# module_board.net
KiCad netlist of a schematic drawn in Altium Designer
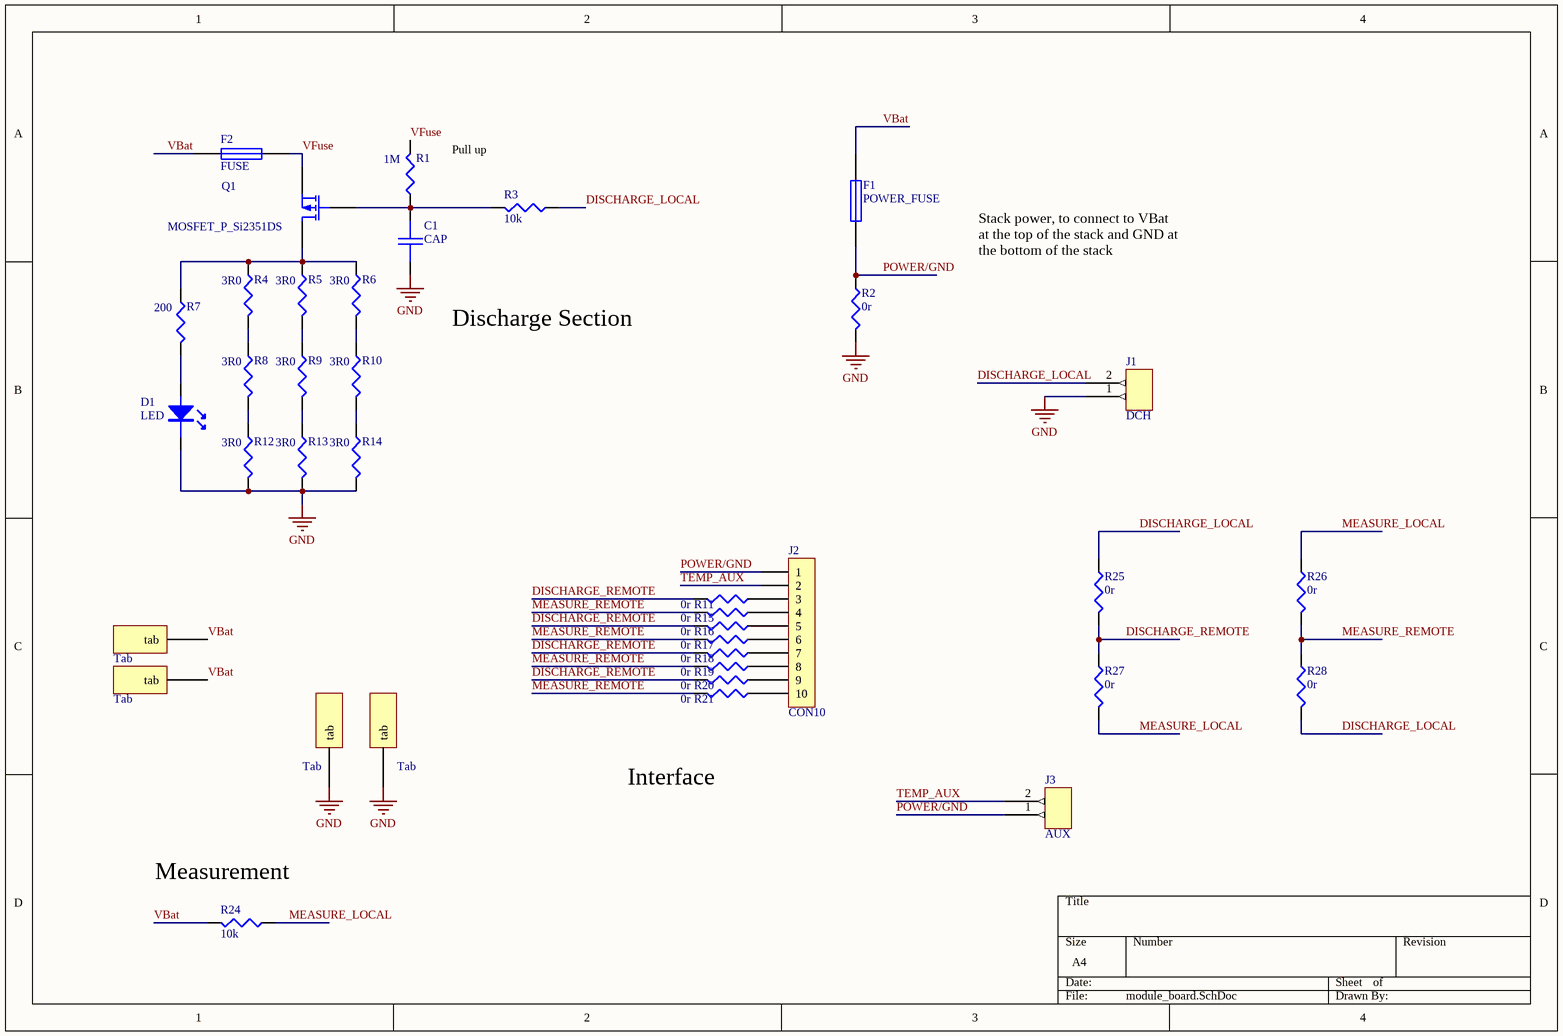
[diagram p0: module_board.SchDoc]

(export (version "E")
  (design (tool "Eeschema 10.0.6"))
  (components
    (comp (ref "C1")
      (value "CAP")
      (footprint "0603")
      (description "Capacitor")
      (libsource (lib "RCLDQ") (part "CAP"))
    )
    (comp (ref "D1") (value "LED") (footprint "0805LED") (libsource (lib "RCLDQ") (part "LED")))
    (comp (ref "F1")
      (value "POWER_FUSE")
      (footprint "1210")
      (description "Fuse")
      (libsource (lib "Miscellaneous") (part "FUSE"))
    )
    (comp (ref "F2")
      (value "FUSE")
      (footprint "LITTELFUSE-154")
      (description "Fuse")
      (libsource (lib "Miscellaneous") (part "FUSE"))
    )
    (comp (ref "J1") (value "DCH") (footprint "IDC2") (libsource (lib "Connectors") (part "CON2")))
    (comp (ref "J2")
      (value "CON10")
      (footprint "IDC10")
      (description "10 pin, right angle, ribbon con with claws")
      (libsource (lib "Connectors") (part "CON10"))
    )
    (comp (ref "J3") (value "AUX") (footprint "IDC2") (libsource (lib "Connectors") (part "CON2")))
    (comp (ref "J4") (value "Tab") (footprint "tab_connect") (libsource (lib "BMS") (part "tab_connection")))
    (comp (ref "J5") (value "Tab") (footprint "tab_connect") (libsource (lib "BMS") (part "tab_connection")))
    (comp (ref "J6") (value "Tab") (footprint "tab_connect") (libsource (lib "") (part "tab_connection_1")))
    (comp (ref "J7") (value "Tab") (footprint "tab_connect") (libsource (lib "") (part "tab_connection_1")))
    (comp (ref "Q1")
      (value "MOSFET_P_Si2351DS")
      (footprint "SOT23-3")
      (description "Si2351DS P-Channel MOSFET")
      (fields (field (name "PUBLISHER") "Altium Limited"))
      (libsource (lib "RCLDQ") (part "MOSFET_P_Si2351DS"))
    )
    (comp (ref "R1")
      (value "~")
      (footprint "0603")
      (description "Resistor")
      (fields (field (name "RESISTANCE") "1M"))
      (libsource (lib "RCLDQ") (part "RES1"))
    )
    (comp (ref "R2")
      (value "~")
      (footprint "1206")
      (description "Resistor")
      (fields (field (name "RESISTANCE") "0r"))
      (libsource (lib "RCLDQ") (part "RES1"))
    )
    (comp (ref "R3")
      (value "~")
      (footprint "0603")
      (description "Resistor")
      (fields (field (name "RESISTANCE") "10k"))
      (libsource (lib "RCLDQ") (part "RES1"))
    )
    (comp (ref "R4")
      (value "3R0")
      (footprint "2512")
      (description "Resistor")
      (libsource (lib "RCLDQ") (part "RES1"))
    )
    (comp (ref "R5")
      (value "3R0")
      (footprint "2512")
      (description "Resistor")
      (libsource (lib "RCLDQ") (part "RES1"))
    )
    (comp (ref "R6")
      (value "3R0")
      (footprint "2512")
      (description "Resistor")
      (libsource (lib "RCLDQ") (part "RES1"))
    )
    (comp (ref "R7")
      (value "200")
      (footprint "0603")
      (description "Resistor")
      (libsource (lib "RCLDQ") (part "RES1"))
    )
    (comp (ref "R8")
      (value "3R0")
      (footprint "2512")
      (description "Resistor")
      (libsource (lib "RCLDQ") (part "RES1"))
    )
    (comp (ref "R9")
      (value "3R0")
      (footprint "2512")
      (description "Resistor")
      (libsource (lib "RCLDQ") (part "RES1"))
    )
    (comp (ref "R10")
      (value "3R0")
      (footprint "2512")
      (description "Resistor")
      (libsource (lib "RCLDQ") (part "RES1"))
    )
    (comp (ref "R11")
      (value "~")
      (footprint "0603")
      (description "Resistor")
      (fields (field (name "RESISTANCE") "0r"))
      (libsource (lib "RCLDQ") (part "RES1"))
    )
    (comp (ref "R12")
      (value "3R0")
      (footprint "2512")
      (description "Resistor")
      (libsource (lib "RCLDQ") (part "RES1"))
    )
    (comp (ref "R13")
      (value "3R0")
      (footprint "2512")
      (description "Resistor")
      (libsource (lib "RCLDQ") (part "RES1"))
    )
    (comp (ref "R14")
      (value "3R0")
      (footprint "2512")
      (description "Resistor")
      (libsource (lib "RCLDQ") (part "RES1"))
    )
    (comp (ref "R15")
      (value "~")
      (footprint "0603")
      (description "Resistor")
      (fields (field (name "RESISTANCE") "0r"))
      (libsource (lib "RCLDQ") (part "RES1"))
    )
    (comp (ref "R16")
      (value "~")
      (footprint "0603")
      (description "Resistor")
      (fields (field (name "RESISTANCE") "0r"))
      (libsource (lib "RCLDQ") (part "RES1"))
    )
    (comp (ref "R17")
      (value "~")
      (footprint "0603")
      (description "Resistor")
      (fields (field (name "RESISTANCE") "0r"))
      (libsource (lib "RCLDQ") (part "RES1"))
    )
    (comp (ref "R18")
      (value "~")
      (footprint "0603")
      (description "Resistor")
      (fields (field (name "RESISTANCE") "0r"))
      (libsource (lib "RCLDQ") (part "RES1"))
    )
    (comp (ref "R19")
      (value "~")
      (footprint "0603")
      (description "Resistor")
      (fields (field (name "RESISTANCE") "0r"))
      (libsource (lib "RCLDQ") (part "RES1"))
    )
    (comp (ref "R20")
      (value "~")
      (footprint "0603")
      (description "Resistor")
      (fields (field (name "RESISTANCE") "0r"))
      (libsource (lib "RCLDQ") (part "RES1"))
    )
    (comp (ref "R21")
      (value "~")
      (footprint "0603")
      (description "Resistor")
      (fields (field (name "RESISTANCE") "0r"))
      (libsource (lib "RCLDQ") (part "RES1"))
    )
    (comp (ref "R24")
      (value "~")
      (footprint "0603")
      (description "Resistor")
      (fields (field (name "RESISTANCE") "10k"))
      (libsource (lib "RCLDQ") (part "RES1"))
    )
    (comp (ref "R25")
      (value "~")
      (footprint "0603")
      (description "Resistor")
      (fields (field (name "RESISTANCE") "0r"))
      (libsource (lib "RCLDQ") (part "RES1"))
    )
    (comp (ref "R26")
      (value "~")
      (footprint "0603")
      (description "Resistor")
      (fields (field (name "RESISTANCE") "0r"))
      (libsource (lib "RCLDQ") (part "RES1"))
    )
    (comp (ref "R27")
      (value "~")
      (footprint "0603")
      (description "Resistor")
      (fields (field (name "RESISTANCE") "0r"))
      (libsource (lib "RCLDQ") (part "RES1"))
    )
    (comp (ref "R28")
      (value "~")
      (footprint "0603")
      (description "Resistor")
      (fields (field (name "RESISTANCE") "0r"))
      (libsource (lib "RCLDQ") (part "RES1"))
    )
  )
  (nets
    (net (code "1") (name "/DISCHARGE_LOCAL") (class "Default")
      (node (ref "J1") (pin "2") (pinfunction "2_2") (pintype "output"))
      (node (ref "R25") (pin "1") (pinfunction "1_1") (pintype "passive"))
      (node (ref "R28") (pin "2") (pinfunction "2_2") (pintype "passive"))
      (node (ref "R3") (pin "1") (pinfunction "1_1") (pintype "passive"))
    )
    (net (code "2") (name "/DISCHARGE_REMOTE") (class "Default")
      (node (ref "R11") (pin "2") (pinfunction "2_2") (pintype "passive"))
      (node (ref "R16") (pin "2") (pinfunction "2_2") (pintype "passive"))
      (node (ref "R18") (pin "2") (pinfunction "2_2") (pintype "passive"))
      (node (ref "R20") (pin "2") (pinfunction "2_2") (pintype "passive"))
      (node (ref "R25") (pin "2") (pinfunction "2_2") (pintype "passive"))
      (node (ref "R27") (pin "1") (pinfunction "1_1") (pintype "passive"))
    )
    (net (code "3") (name "/MEASURE_LOCAL") (class "Default")
      (node (ref "R24") (pin "1") (pinfunction "1_1") (pintype "passive"))
      (node (ref "R26") (pin "1") (pinfunction "1_1") (pintype "passive"))
      (node (ref "R27") (pin "2") (pinfunction "2_2") (pintype "passive"))
    )
    (net (code "4") (name "/MEASURE_REMOTE") (class "Default")
      (node (ref "R15") (pin "2") (pinfunction "2_2") (pintype "passive"))
      (node (ref "R17") (pin "2") (pinfunction "2_2") (pintype "passive"))
      (node (ref "R19") (pin "2") (pinfunction "2_2") (pintype "passive"))
      (node (ref "R21") (pin "2") (pinfunction "2_2") (pintype "passive"))
      (node (ref "R26") (pin "2") (pinfunction "2_2") (pintype "passive"))
      (node (ref "R28") (pin "1") (pinfunction "1_1") (pintype "passive"))
    )
    (net (code "5") (name "/POWER{slash}GND") (class "Default")
      (node (ref "F1") (pin "1") (pinfunction "1_1") (pintype "passive"))
      (node (ref "J2") (pin "1") (pinfunction "1_1") (pintype "passive"))
      (node (ref "J3") (pin "1") (pinfunction "1_1") (pintype "output"))
      (node (ref "R2") (pin "1") (pinfunction "1_1") (pintype "passive"))
    )
    (net (code "6") (name "/TEMP_AUX") (class "Default")
      (node (ref "J2") (pin "2") (pinfunction "2_2") (pintype "passive"))
      (node (ref "J3") (pin "2") (pinfunction "2_2") (pintype "output"))
    )
    (net (code "7") (name "/VBat") (class "Default")
      (node (ref "F1") (pin "2") (pinfunction "2_2") (pintype "passive"))
      (node (ref "F2") (pin "1") (pinfunction "1_1") (pintype "passive"))
      (node (ref "J4") (pin "0") (pinfunction "tab_0") (pintype "passive"))
      (node (ref "J5") (pin "0") (pinfunction "tab_0") (pintype "passive"))
      (node (ref "R24") (pin "2") (pinfunction "2_2") (pintype "passive"))
    )
    (net (code "8") (name "/VFuse") (class "Default")
      (node (ref "F2") (pin "2") (pinfunction "2_2") (pintype "passive"))
      (node (ref "Q1") (pin "2") (pinfunction "S_2") (pintype "passive"))
      (node (ref "R1") (pin "2") (pinfunction "2_2") (pintype "passive"))
    )
    (net (code "9") (name "GND") (class "Default")
      (node (ref "C1") (pin "2") (pinfunction "2_2") (pintype "passive"))
      (node (ref "D1") (pin "K") (pinfunction "K_K") (pintype "passive"))
      (node (ref "J1") (pin "1") (pinfunction "1_1") (pintype "output"))
      (node (ref "J6") (pin "0") (pinfunction "tab_0") (pintype "passive"))
      (node (ref "J7") (pin "0") (pinfunction "tab_0") (pintype "passive"))
      (node (ref "R12") (pin "2") (pinfunction "2_2") (pintype "passive"))
      (node (ref "R13") (pin "2") (pinfunction "2_2") (pintype "passive"))
      (node (ref "R14") (pin "2") (pinfunction "2_2") (pintype "passive"))
      (node (ref "R2") (pin "2") (pinfunction "2_2") (pintype "passive"))
    )
    (net (code "10") (name "Net-(D1-PadA)") (class "Default")
      (node (ref "D1") (pin "A") (pinfunction "A_A") (pintype "passive"))
      (node (ref "R7") (pin "2") (pinfunction "2_2") (pintype "passive"))
    )
    (net (code "11") (name "Net-(J2-Pad3)") (class "Default")
      (node (ref "J2") (pin "3") (pinfunction "3_3") (pintype "passive"))
      (node (ref "R11") (pin "1") (pinfunction "1_1") (pintype "passive"))
    )
    (net (code "12") (name "Net-(J2-Pad4)") (class "Default")
      (node (ref "J2") (pin "4") (pinfunction "4_4") (pintype "passive"))
      (node (ref "R15") (pin "1") (pinfunction "1_1") (pintype "passive"))
    )
    (net (code "13") (name "Net-(J2-Pad5)") (class "Default")
      (node (ref "J2") (pin "5") (pinfunction "5_5") (pintype "passive"))
      (node (ref "R16") (pin "1") (pinfunction "1_1") (pintype "passive"))
    )
    (net (code "14") (name "Net-(J2-Pad6)") (class "Default")
      (node (ref "J2") (pin "6") (pinfunction "6_6") (pintype "passive"))
      (node (ref "R17") (pin "1") (pinfunction "1_1") (pintype "passive"))
    )
    (net (code "15") (name "Net-(J2-Pad7)") (class "Default")
      (node (ref "J2") (pin "7") (pinfunction "7_7") (pintype "passive"))
      (node (ref "R18") (pin "1") (pinfunction "1_1") (pintype "passive"))
    )
    (net (code "16") (name "Net-(J2-Pad8)") (class "Default")
      (node (ref "J2") (pin "8") (pinfunction "8_8") (pintype "passive"))
      (node (ref "R19") (pin "1") (pinfunction "1_1") (pintype "passive"))
    )
    (net (code "17") (name "Net-(J2-Pad9)") (class "Default")
      (node (ref "J2") (pin "9") (pinfunction "9_9") (pintype "passive"))
      (node (ref "R20") (pin "1") (pinfunction "1_1") (pintype "passive"))
    )
    (net (code "18") (name "Net-(J2-Pad10)") (class "Default")
      (node (ref "J2") (pin "10") (pinfunction "10_10") (pintype "passive"))
      (node (ref "R21") (pin "1") (pinfunction "1_1") (pintype "passive"))
    )
    (net (code "19") (name "Net-(Q1-D)") (class "Default")
      (node (ref "Q1") (pin "3") (pinfunction "D_3") (pintype "passive"))
      (node (ref "R4") (pin "1") (pinfunction "1_1") (pintype "passive"))
      (node (ref "R5") (pin "1") (pinfunction "1_1") (pintype "passive"))
      (node (ref "R6") (pin "1") (pinfunction "1_1") (pintype "passive"))
      (node (ref "R7") (pin "1") (pinfunction "1_1") (pintype "passive"))
    )
    (net (code "20") (name "Net-(Q1-G)") (class "Default")
      (node (ref "C1") (pin "1") (pinfunction "1_1") (pintype "passive"))
      (node (ref "Q1") (pin "1") (pinfunction "G_1") (pintype "passive"))
      (node (ref "R1") (pin "1") (pinfunction "1_1") (pintype "passive"))
      (node (ref "R3") (pin "2") (pinfunction "2_2") (pintype "passive"))
    )
    (net (code "21") (name "Net-(R4-Pad2)") (class "Default")
      (node (ref "R4") (pin "2") (pinfunction "2_2") (pintype "passive"))
      (node (ref "R8") (pin "1") (pinfunction "1_1") (pintype "passive"))
    )
    (net (code "22") (name "Net-(R5-Pad2)") (class "Default")
      (node (ref "R5") (pin "2") (pinfunction "2_2") (pintype "passive"))
      (node (ref "R9") (pin "1") (pinfunction "1_1") (pintype "passive"))
    )
    (net (code "23") (name "Net-(R10-Pad1)") (class "Default")
      (node (ref "R10") (pin "1") (pinfunction "1_1") (pintype "passive"))
      (node (ref "R6") (pin "2") (pinfunction "2_2") (pintype "passive"))
    )
    (net (code "24") (name "Net-(R10-Pad2)") (class "Default")
      (node (ref "R10") (pin "2") (pinfunction "2_2") (pintype "passive"))
      (node (ref "R14") (pin "1") (pinfunction "1_1") (pintype "passive"))
    )
    (net (code "25") (name "Net-(R12-Pad1)") (class "Default")
      (node (ref "R12") (pin "1") (pinfunction "1_1") (pintype "passive"))
      (node (ref "R8") (pin "2") (pinfunction "2_2") (pintype "passive"))
    )
    (net (code "26") (name "Net-(R13-Pad1)") (class "Default")
      (node (ref "R13") (pin "1") (pinfunction "1_1") (pintype "passive"))
      (node (ref "R9") (pin "2") (pinfunction "2_2") (pintype "passive"))
    )
  )
)
